# ProPrj_Business_Card_Macro_Pad_2025-06-1.net
KiCad netlist of a schematic drawn in EasyEDA Pro
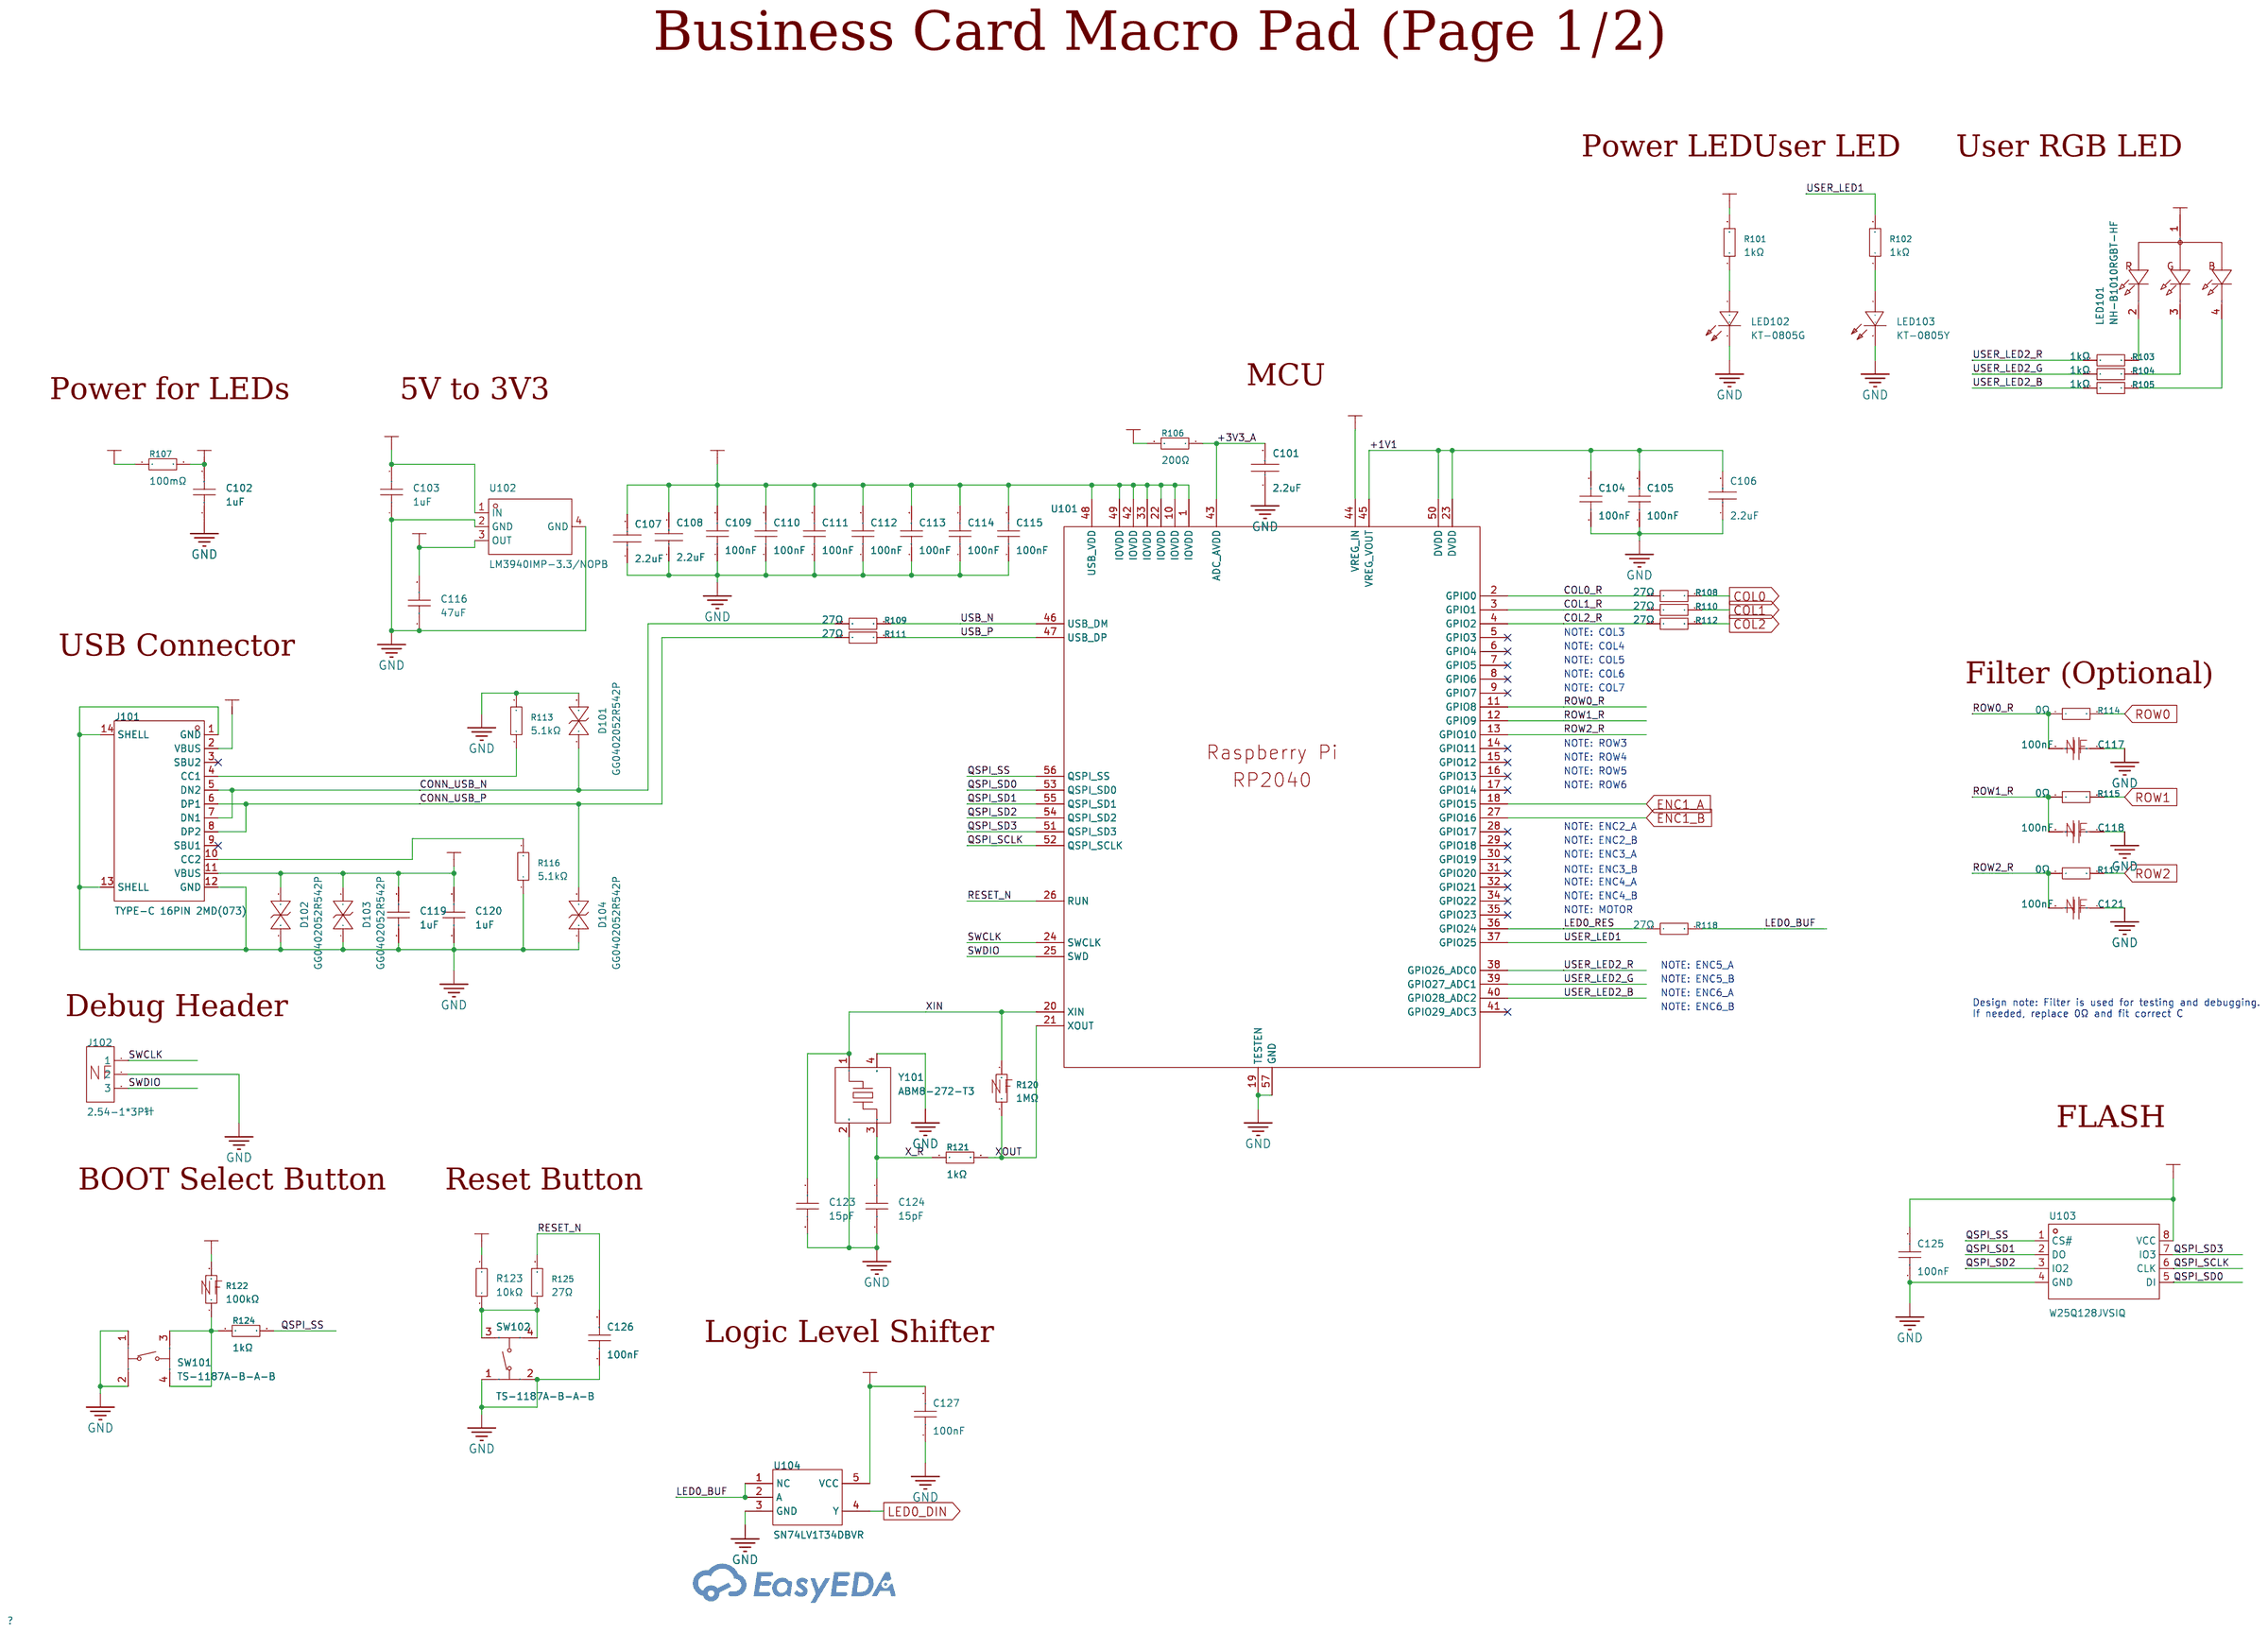
[diagram p0: MCU]
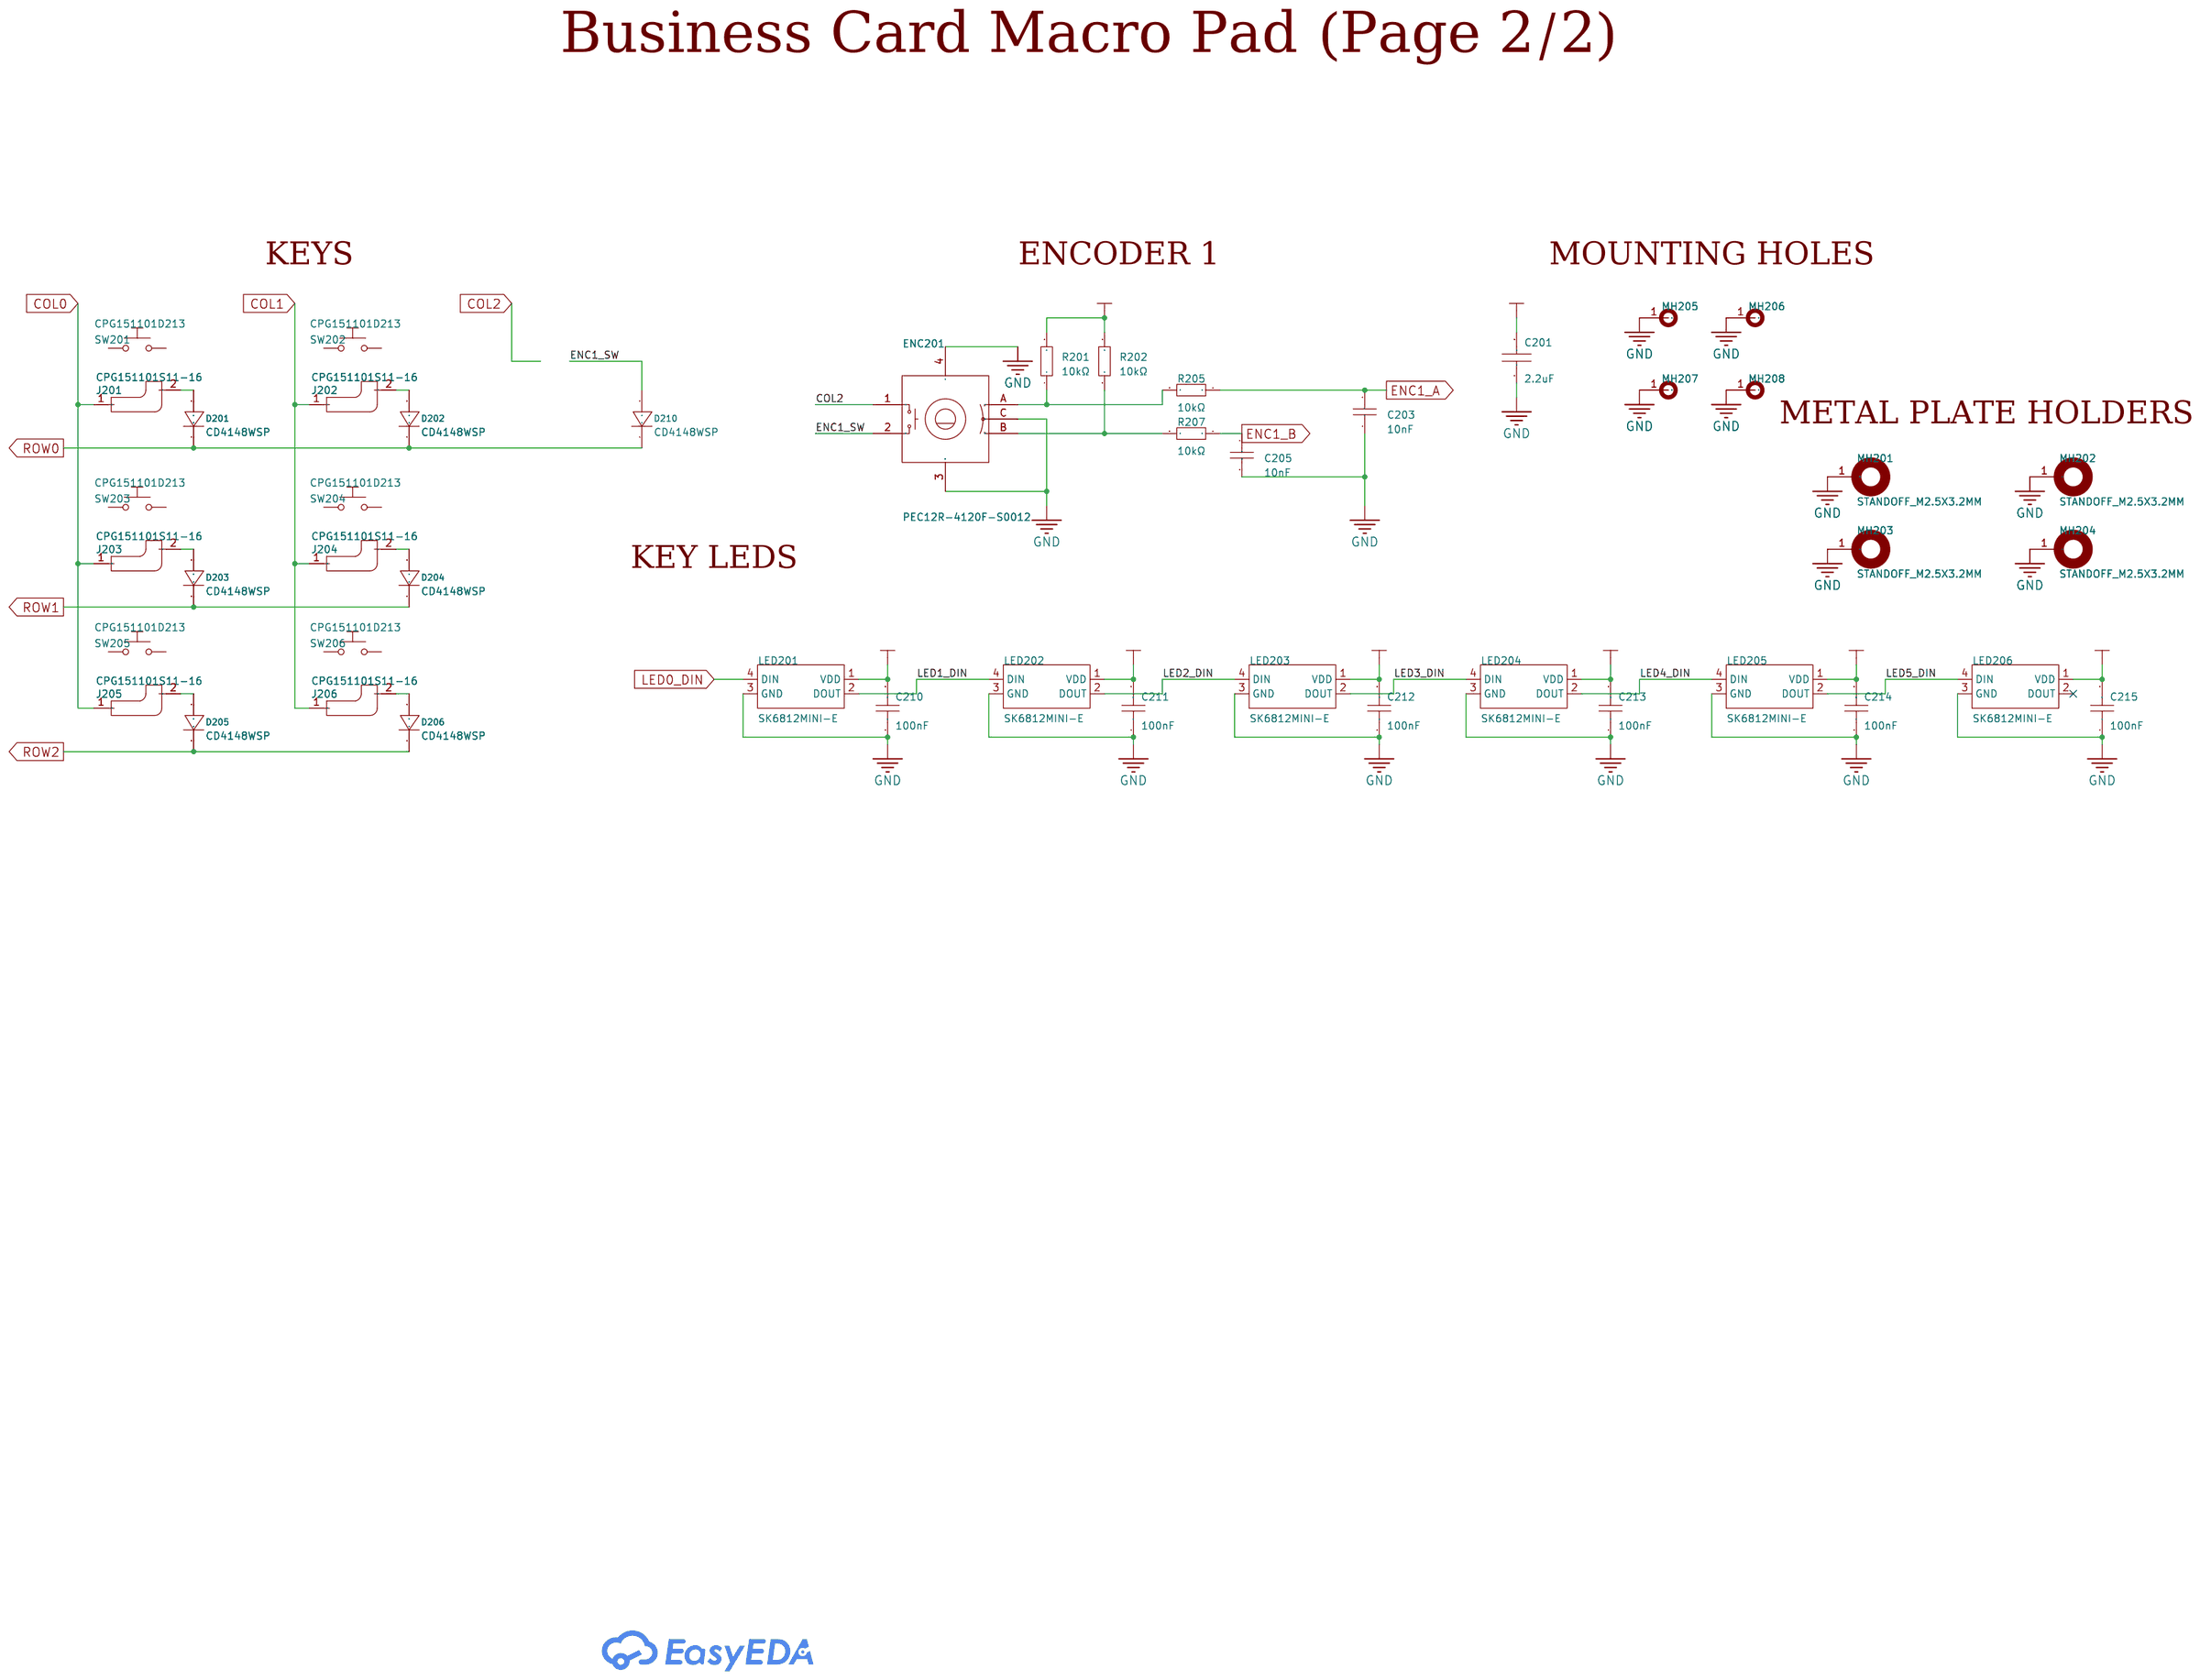
[diagram p1: OTHER]

(export (version "E")
  (design (tool "Eeschema 10.0.6"))
  (components
    (comp (ref "C101")
      (value "2.2uF")
      (footprint "easyedapro:C0402")
      (fields
        (field (name "Manufacturer Part") "CL05A225MQ5NSNC")
        (field (name "Manufacturer") "SAMSUNG(三星)")
      )
      (libsource (lib "easyedapro") (part "CL05A225MQ5NSNC"))
    )
    (comp (ref "C102")
      (value "1uF")
      (footprint "easyedapro:C0402")
      (fields
        (field (name "Manufacturer Part") "CL05A105KA5NQNC")
        (field (name "Manufacturer") "SAMSUNG(三星)")
      )
      (libsource (lib "easyedapro") (part "CL05A105KA5NQNC"))
    )
    (comp (ref "C103")
      (value "1uF")
      (footprint "easyedapro:C0402")
      (fields
        (field (name "Manufacturer Part") "CL05A105KA5NQNC")
        (field (name "Manufacturer") "SAMSUNG(三星)")
      )
      (libsource (lib "easyedapro") (part "CL05A105KA5NQNC"))
    )
    (comp (ref "C104")
      (value "100nF")
      (footprint "easyedapro:C0402")
      (fields
        (field (name "Manufacturer Part") "CL05B104KO5NNNC")
        (field (name "Manufacturer") "SAMSUNG(三星)")
      )
      (libsource (lib "easyedapro") (part "CL05B104KO5NNNC"))
    )
    (comp (ref "C105")
      (value "100nF")
      (footprint "easyedapro:C0402")
      (fields
        (field (name "Manufacturer Part") "CL05B104KO5NNNC")
        (field (name "Manufacturer") "SAMSUNG(三星)")
      )
      (libsource (lib "easyedapro") (part "CL05B104KO5NNNC"))
    )
    (comp (ref "C106")
      (value "2.2uF")
      (footprint "easyedapro:C0402")
      (fields
        (field (name "Manufacturer Part") "CL05A225MQ5NSNC")
        (field (name "Manufacturer") "SAMSUNG(三星)")
      )
      (libsource (lib "easyedapro") (part "CL05A225MQ5NSNC"))
    )
    (comp (ref "C107")
      (value "2.2uF")
      (footprint "easyedapro:C0402")
      (fields
        (field (name "Manufacturer Part") "CL05A225MQ5NSNC")
        (field (name "Manufacturer") "SAMSUNG(三星)")
      )
      (libsource (lib "easyedapro") (part "CL05A225MQ5NSNC"))
    )
    (comp (ref "C108")
      (value "2.2uF")
      (footprint "easyedapro:C0402")
      (fields
        (field (name "Manufacturer Part") "CL05A225MQ5NSNC")
        (field (name "Manufacturer") "SAMSUNG(三星)")
      )
      (libsource (lib "easyedapro") (part "CL05A225MQ5NSNC"))
    )
    (comp (ref "C109")
      (value "100nF")
      (footprint "easyedapro:C0402")
      (fields
        (field (name "Manufacturer Part") "CL05B104KO5NNNC")
        (field (name "Manufacturer") "SAMSUNG(三星)")
      )
      (libsource (lib "easyedapro") (part "CL05B104KO5NNNC"))
    )
    (comp (ref "C110")
      (value "100nF")
      (footprint "easyedapro:C0402")
      (fields
        (field (name "Manufacturer Part") "CL05B104KO5NNNC")
        (field (name "Manufacturer") "SAMSUNG(三星)")
      )
      (libsource (lib "easyedapro") (part "CL05B104KO5NNNC"))
    )
    (comp (ref "C111")
      (value "100nF")
      (footprint "easyedapro:C0402")
      (fields
        (field (name "Manufacturer Part") "CL05B104KO5NNNC")
        (field (name "Manufacturer") "SAMSUNG(三星)")
      )
      (libsource (lib "easyedapro") (part "CL05B104KO5NNNC"))
    )
    (comp (ref "C112")
      (value "100nF")
      (footprint "easyedapro:C0402")
      (fields
        (field (name "Manufacturer Part") "CL05B104KO5NNNC")
        (field (name "Manufacturer") "SAMSUNG(三星)")
      )
      (libsource (lib "easyedapro") (part "CL05B104KO5NNNC"))
    )
    (comp (ref "C113")
      (value "100nF")
      (footprint "easyedapro:C0402")
      (fields
        (field (name "Manufacturer Part") "CL05B104KO5NNNC")
        (field (name "Manufacturer") "SAMSUNG(三星)")
      )
      (libsource (lib "easyedapro") (part "CL05B104KO5NNNC"))
    )
    (comp (ref "C114")
      (value "100nF")
      (footprint "easyedapro:C0402")
      (fields
        (field (name "Manufacturer Part") "CL05B104KO5NNNC")
        (field (name "Manufacturer") "SAMSUNG(三星)")
      )
      (libsource (lib "easyedapro") (part "CL05B104KO5NNNC"))
    )
    (comp (ref "C115")
      (value "100nF")
      (footprint "easyedapro:C0402")
      (fields
        (field (name "Manufacturer Part") "CL05B104KO5NNNC")
        (field (name "Manufacturer") "SAMSUNG(三星)")
      )
      (libsource (lib "easyedapro") (part "CL05B104KO5NNNC"))
    )
    (comp (ref "C116")
      (value "47uF")
      (footprint "easyedapro:C1206")
      (fields
        (field (name "Manufacturer Part") "CL31A476MPHNNNE")
        (field (name "Manufacturer") "SAMSUNG(三星)")
      )
      (libsource (lib "easyedapro") (part "CL31A476MPHNNNE"))
    )
    (comp (ref "C117")
      (value "100nF")
      (footprint "easyedapro:C0402")
      (fields
        (field (name "Manufacturer Part") "CL05B104KO5NNNC")
        (field (name "Manufacturer") "SAMSUNG(三星)")
      )
      (libsource (lib "easyedapro") (part "CL05B104KO5NNNC"))
    )
    (comp (ref "C118")
      (value "100nF")
      (footprint "easyedapro:C0402")
      (fields
        (field (name "Manufacturer Part") "CL05B104KO5NNNC")
        (field (name "Manufacturer") "SAMSUNG(三星)")
      )
      (libsource (lib "easyedapro") (part "CL05B104KO5NNNC"))
    )
    (comp (ref "C119")
      (value "1uF")
      (footprint "easyedapro:C0402")
      (fields
        (field (name "Manufacturer Part") "CL05A105KA5NQNC")
        (field (name "Manufacturer") "SAMSUNG(三星)")
      )
      (libsource (lib "easyedapro") (part "CL05A105KA5NQNC"))
    )
    (comp (ref "C120")
      (value "1uF")
      (footprint "easyedapro:C0402")
      (fields
        (field (name "Manufacturer Part") "CL05A105KA5NQNC")
        (field (name "Manufacturer") "SAMSUNG(三星)")
      )
      (libsource (lib "easyedapro") (part "CL05A105KA5NQNC"))
    )
    (comp (ref "C121")
      (value "100nF")
      (footprint "easyedapro:C0402")
      (fields
        (field (name "Manufacturer Part") "CL05B104KO5NNNC")
        (field (name "Manufacturer") "SAMSUNG(三星)")
      )
      (libsource (lib "easyedapro") (part "CL05B104KO5NNNC"))
    )
    (comp (ref "C123")
      (value "15pF")
      (footprint "easyedapro:C0402")
      (fields
        (field (name "Manufacturer Part") "CL05C150JB5NNNC")
        (field (name "Manufacturer") "SAMSUNG(三星)")
      )
      (libsource (lib "easyedapro") (part "CL05C150JB5NNNC"))
    )
    (comp (ref "C124")
      (value "15pF")
      (footprint "easyedapro:C0402")
      (fields
        (field (name "Manufacturer Part") "CL05C150JB5NNNC")
        (field (name "Manufacturer") "SAMSUNG(三星)")
      )
      (libsource (lib "easyedapro") (part "CL05C150JB5NNNC"))
    )
    (comp (ref "C125")
      (value "100nF")
      (footprint "easyedapro:C0402")
      (fields
        (field (name "Manufacturer Part") "CL05B104KO5NNNC")
        (field (name "Manufacturer") "SAMSUNG(三星)")
      )
      (libsource (lib "easyedapro") (part "CL05B104KO5NNNC"))
    )
    (comp (ref "C126")
      (value "100nF")
      (footprint "easyedapro:C0402")
      (fields
        (field (name "Manufacturer Part") "CL05B104KO5NNNC")
        (field (name "Manufacturer") "SAMSUNG(三星)")
      )
      (libsource (lib "easyedapro") (part "CL05B104KO5NNNC"))
    )
    (comp (ref "C127")
      (value "100nF")
      (footprint "easyedapro:C0402")
      (fields
        (field (name "Manufacturer Part") "CL05B104KO5NNNC")
        (field (name "Manufacturer") "SAMSUNG(三星)")
      )
      (libsource (lib "easyedapro") (part "CL05B104KO5NNNC"))
    )
    (comp (ref "D101")
      (value "GG0402052R542P")
      (footprint "easyedapro:D0402-BI")
      (fields (field (name "Manufacturer") "Kyocera AVX"))
      (libsource (lib "easyedapro") (part "GG0402052R542P"))
    )
    (comp (ref "D102")
      (value "GG0402052R542P")
      (footprint "easyedapro:D0402-BI")
      (fields (field (name "Manufacturer") "Kyocera AVX"))
      (libsource (lib "easyedapro") (part "GG0402052R542P"))
    )
    (comp (ref "D103")
      (value "GG0402052R542P")
      (footprint "easyedapro:D0402-BI")
      (fields (field (name "Manufacturer") "Kyocera AVX"))
      (libsource (lib "easyedapro") (part "GG0402052R542P"))
    )
    (comp (ref "D104")
      (value "GG0402052R542P")
      (footprint "easyedapro:D0402-BI")
      (fields (field (name "Manufacturer") "Kyocera AVX"))
      (libsource (lib "easyedapro") (part "GG0402052R542P"))
    )
    (comp (ref "J101")
      (value "TYPE-C 16PIN 2MD(073)")
      (footprint "easyedapro:USB-C-SMD_TYPE-C-6PIN-2MD-073")
      (fields (field (name "Manufacturer") "SHOU HAN(首韩)"))
      (libsource (lib "easyedapro") (part "TYPE-C 16PIN 2MD(073)"))
    )
    (comp (ref "J102")
      (value "2.54-1*3P针")
      (footprint "easyedapro:HDR-TH_3P-P2.54-V-M-1")
      (fields (field (name "Manufacturer") "BOOMELE(博穆精密)"))
      (libsource (lib "easyedapro") (part "Header-Male-2.54_1x3"))
    )
    (comp (ref "LED101")
      (value "NH-B1010RGBT-HF")
      (footprint "easyedapro:LED-ARRAY-SMD_4P-L1.0-W1.0-TR_NH-B1010RGBT")
      (fields (field (name "Manufacturer") "国星光电"))
      (libsource (lib "easyedapro") (part "NH-B1010RGBT-HF_JO_v1.0"))
    )
    (comp (ref "LED102")
      (value "KT-0805G")
      (footprint "easyedapro:LED0805-R-RD")
      (fields (field (name "Manufacturer") "KENTO"))
      (libsource (lib "easyedapro") (part "0805G (Green)"))
    )
    (comp (ref "LED103")
      (value "KT-0805Y")
      (footprint "easyedapro:LED0805-R-RD")
      (fields (field (name "Manufacturer") "KENTO"))
      (libsource (lib "easyedapro") (part "17-21SUYC/TR8"))
    )
    (comp (ref "R101")
      (value "1kΩ")
      (footprint "easyedapro:R0402")
      (fields
        (field (name "Manufacturer Part") "0402WGF1001TCE")
        (field (name "Manufacturer") "UNI-ROYAL(厚声)")
      )
      (libsource (lib "easyedapro") (part "0402WGF1001TCE"))
    )
    (comp (ref "R102")
      (value "1kΩ")
      (footprint "easyedapro:R0402")
      (fields
        (field (name "Manufacturer Part") "0402WGF1001TCE")
        (field (name "Manufacturer") "UNI-ROYAL(厚声)")
      )
      (libsource (lib "easyedapro") (part "0402WGF1001TCE"))
    )
    (comp (ref "R103")
      (value "1kΩ")
      (footprint "easyedapro:R0402")
      (fields
        (field (name "Manufacturer Part") "0402WGF1001TCE")
        (field (name "Manufacturer") "UNI-ROYAL(厚声)")
      )
      (libsource (lib "easyedapro") (part "0402WGF1001TCE"))
    )
    (comp (ref "R104")
      (value "1kΩ")
      (footprint "easyedapro:R0402")
      (fields
        (field (name "Manufacturer Part") "0402WGF1001TCE")
        (field (name "Manufacturer") "UNI-ROYAL(厚声)")
      )
      (libsource (lib "easyedapro") (part "0402WGF1001TCE"))
    )
    (comp (ref "R105")
      (value "1kΩ")
      (footprint "easyedapro:R0402")
      (fields
        (field (name "Manufacturer Part") "0402WGF1001TCE")
        (field (name "Manufacturer") "UNI-ROYAL(厚声)")
      )
      (libsource (lib "easyedapro") (part "0402WGF1001TCE"))
    )
    (comp (ref "R106")
      (value "200Ω")
      (footprint "easyedapro:R0402")
      (fields
        (field (name "Manufacturer Part") "0402WGF2000TCE")
        (field (name "Manufacturer") "UNI-ROYAL(厚声)")
      )
      (libsource (lib "easyedapro") (part "0402WGF2000TCE"))
    )
    (comp (ref "R107")
      (value "100mΩ")
      (footprint "easyedapro:R1206")
      (fields
        (field (name "Manufacturer Part") "1206W4F100LT5E")
        (field (name "Manufacturer") "UNI-ROYAL(厚声)")
      )
      (libsource (lib "easyedapro") (part "1206W4F100LT5E"))
    )
    (comp (ref "R108")
      (value "27Ω")
      (footprint "easyedapro:R0402")
      (fields
        (field (name "Manufacturer Part") "0402WGF270JTCE")
        (field (name "Manufacturer") "UNI-ROYAL(厚声)")
      )
      (libsource (lib "easyedapro") (part "0402WGF270JTCE"))
    )
    (comp (ref "R109")
      (value "27Ω")
      (footprint "easyedapro:R0402")
      (fields
        (field (name "Manufacturer Part") "0402WGF270JTCE")
        (field (name "Manufacturer") "UNI-ROYAL(厚声)")
      )
      (libsource (lib "easyedapro") (part "0402WGF270JTCE"))
    )
    (comp (ref "R110")
      (value "27Ω")
      (footprint "easyedapro:R0402")
      (fields
        (field (name "Manufacturer Part") "0402WGF270JTCE")
        (field (name "Manufacturer") "UNI-ROYAL(厚声)")
      )
      (libsource (lib "easyedapro") (part "0402WGF270JTCE"))
    )
    (comp (ref "R111")
      (value "27Ω")
      (footprint "easyedapro:R0402")
      (fields
        (field (name "Manufacturer Part") "0402WGF270JTCE")
        (field (name "Manufacturer") "UNI-ROYAL(厚声)")
      )
      (libsource (lib "easyedapro") (part "0402WGF270JTCE"))
    )
    (comp (ref "R112")
      (value "27Ω")
      (footprint "easyedapro:R0402")
      (fields
        (field (name "Manufacturer Part") "0402WGF270JTCE")
        (field (name "Manufacturer") "UNI-ROYAL(厚声)")
      )
      (libsource (lib "easyedapro") (part "0402WGF270JTCE"))
    )
    (comp (ref "R113")
      (value "5.1kΩ")
      (footprint "easyedapro:R0402")
      (fields
        (field (name "Manufacturer Part") "0402WGF5101TCE")
        (field (name "Manufacturer") "UNI-ROYAL(厚声)")
      )
      (libsource (lib "easyedapro") (part "0402WGF5101TCE"))
    )
    (comp (ref "R114")
      (value "0Ω")
      (footprint "easyedapro:R0402")
      (fields
        (field (name "Manufacturer Part") "0402WGF0000TCE")
        (field (name "Manufacturer") "UNI-ROYAL(厚声)")
      )
      (libsource (lib "easyedapro") (part "0402WGF0000TCE"))
    )
    (comp (ref "R115")
      (value "0Ω")
      (footprint "easyedapro:R0402")
      (fields
        (field (name "Manufacturer Part") "0402WGF0000TCE")
        (field (name "Manufacturer") "UNI-ROYAL(厚声)")
      )
      (libsource (lib "easyedapro") (part "0402WGF0000TCE"))
    )
    (comp (ref "R116")
      (value "5.1kΩ")
      (footprint "easyedapro:R0402")
      (fields
        (field (name "Manufacturer Part") "0402WGF5101TCE")
        (field (name "Manufacturer") "UNI-ROYAL(厚声)")
      )
      (libsource (lib "easyedapro") (part "0402WGF5101TCE"))
    )
    (comp (ref "R117")
      (value "0Ω")
      (footprint "easyedapro:R0402")
      (fields
        (field (name "Manufacturer Part") "0402WGF0000TCE")
        (field (name "Manufacturer") "UNI-ROYAL(厚声)")
      )
      (libsource (lib "easyedapro") (part "0402WGF0000TCE"))
    )
    (comp (ref "R118")
      (value "27Ω")
      (footprint "easyedapro:R0402")
      (fields
        (field (name "Manufacturer Part") "0402WGF270JTCE")
        (field (name "Manufacturer") "UNI-ROYAL(厚声)")
      )
      (libsource (lib "easyedapro") (part "0402WGF270JTCE"))
    )
    (comp (ref "R120")
      (value "1MΩ")
      (footprint "easyedapro:R0402")
      (fields
        (field (name "Manufacturer Part") "0402WGF1004TCE")
        (field (name "Manufacturer") "UNI-ROYAL(厚声)")
      )
      (libsource (lib "easyedapro") (part "0402WGF1004TCE"))
    )
    (comp (ref "R121")
      (value "1kΩ")
      (footprint "easyedapro:R0402")
      (fields
        (field (name "Manufacturer Part") "0402WGF1001TCE")
        (field (name "Manufacturer") "UNI-ROYAL(厚声)")
      )
      (libsource (lib "easyedapro") (part "0402WGF1001TCE"))
    )
    (comp (ref "R122")
      (value "100kΩ")
      (footprint "easyedapro:R0402")
      (fields
        (field (name "Manufacturer Part") "0402WGF1003TCE")
        (field (name "Manufacturer") "UNI-ROYAL(厚声)")
      )
      (libsource (lib "easyedapro") (part "0402WGF1003TCE"))
    )
    (comp (ref "R123")
      (value "10kΩ")
      (footprint "easyedapro:R0402")
      (fields
        (field (name "Manufacturer Part") "0402WGF1002TCE")
        (field (name "Manufacturer") "UNI-ROYAL(厚声)")
      )
      (libsource (lib "easyedapro") (part "0402WGF1002TCE"))
    )
    (comp (ref "R124")
      (value "1kΩ")
      (footprint "easyedapro:R0402")
      (fields
        (field (name "Manufacturer Part") "0402WGF1001TCE")
        (field (name "Manufacturer") "UNI-ROYAL(厚声)")
      )
      (libsource (lib "easyedapro") (part "0402WGF1001TCE"))
    )
    (comp (ref "R125")
      (value "27Ω")
      (footprint "easyedapro:R0402")
      (fields
        (field (name "Manufacturer Part") "0402WGF270JTCE")
        (field (name "Manufacturer") "UNI-ROYAL(厚声)")
      )
      (libsource (lib "easyedapro") (part "0402WGF270JTCE"))
    )
    (comp (ref "SW101")
      (value "TS-1187A-B-A-B")
      (footprint "easyedapro:SW-SMD_4P-L5.1-W5.1-P3.70-LS6.5-TL_H1.5")
      (fields (field (name "Manufacturer") "XKB Connectivity(中国星坤)"))
      (libsource (lib "easyedapro") (part "TS-1187A-B-A-B"))
    )
    (comp (ref "SW102")
      (value "TS-1187A-B-A-B")
      (footprint "easyedapro:SW-SMD_4P-L5.1-W5.1-P3.70-LS6.5-TL_H1.5")
      (fields (field (name "Manufacturer") "XKB Connectivity(中国星坤)"))
      (libsource (lib "easyedapro") (part "TS-1187A-B-A-B"))
    )
    (comp (ref "U101")
      (value "RP2040")
      (footprint "easyedapro:LQFN-56_L7.0-W7.0-P0.4-EP")
      (fields (field (name "Manufacturer") "Raspberry Pi(树莓派)"))
      (libsource (lib "easyedapro") (part "RP2040_C2040_jo_v1.0"))
    )
    (comp (ref "U102")
      (value "LM3940IMP-3.3/NOPB")
      (footprint "easyedapro:SOT-223_L6.5-W3.5-P2.30-LS7.0-BR")
      (fields (field (name "Manufacturer") "TI(德州仪器)"))
      (libsource (lib "easyedapro") (part "LM3940IMP-3.3/NOPB"))
    )
    (comp (ref "U103")
      (value "W25Q128JVSIQ")
      (footprint "easyedapro:SOIC-8_L5.3-W5.3-P1.27-LS8.0-BL")
      (fields (field (name "Manufacturer") "WINBOND(华邦)"))
      (libsource (lib "easyedapro") (part "W25Q128JVSIQTR"))
    )
    (comp (ref "U104")
      (value "SN74LV1T34DBVR")
      (footprint "easyedapro:SOT-23-5_L2.9-W1.6-P0.95-LS2.8-BR")
      (fields (field (name "Manufacturer") "TI(德州仪器)"))
      (libsource (lib "easyedapro") (part "SN74LV1T34DBVR_JO_v1.0"))
    )
    (comp (ref "Y101")
      (value "ABM8-272-T3")
      (footprint "easyedapro:CRYSTAL-SMD_4P-L3.2-W2.5-BL")
      (fields (field (name "Manufacturer") "ABRACON"))
      (libsource (lib "easyedapro") (part "ABM8-272-T3_C20625731"))
    )
    (comp (ref "C201")
      (value "2.2uF")
      (footprint "easyedapro:C0402")
      (fields
        (field (name "Manufacturer Part") "CL05A225MQ5NSNC")
        (field (name "Manufacturer") "SAMSUNG(三星)")
      )
      (libsource (lib "easyedapro") (part "CL05A225MQ5NSNC"))
    )
    (comp (ref "C203")
      (value "10nF")
      (footprint "easyedapro:C0402")
      (fields
        (field (name "Manufacturer Part") "CL05B103KB5NNNC")
        (field (name "Manufacturer") "SAMSUNG(三星)")
      )
      (libsource (lib "easyedapro") (part "CL05B103KB5NNNC"))
    )
    (comp (ref "C205")
      (value "10nF")
      (footprint "easyedapro:C0402")
      (fields
        (field (name "Manufacturer Part") "CL05B103KB5NNNC")
        (field (name "Manufacturer") "SAMSUNG(三星)")
      )
      (libsource (lib "easyedapro") (part "CL05B103KB5NNNC"))
    )
    (comp (ref "C210")
      (value "100nF")
      (footprint "easyedapro:C0402")
      (fields
        (field (name "Manufacturer Part") "CL05B104KO5NNNC")
        (field (name "Manufacturer") "SAMSUNG(三星)")
      )
      (libsource (lib "easyedapro") (part "CL05B104KO5NNNC"))
    )
    (comp (ref "C211")
      (value "100nF")
      (footprint "easyedapro:C0402")
      (fields
        (field (name "Manufacturer Part") "CL05B104KO5NNNC")
        (field (name "Manufacturer") "SAMSUNG(三星)")
      )
      (libsource (lib "easyedapro") (part "CL05B104KO5NNNC"))
    )
    (comp (ref "C212")
      (value "100nF")
      (footprint "easyedapro:C0402")
      (fields
        (field (name "Manufacturer Part") "CL05B104KO5NNNC")
        (field (name "Manufacturer") "SAMSUNG(三星)")
      )
      (libsource (lib "easyedapro") (part "CL05B104KO5NNNC"))
    )
    (comp (ref "C213")
      (value "100nF")
      (footprint "easyedapro:C0402")
      (fields
        (field (name "Manufacturer Part") "CL05B104KO5NNNC")
        (field (name "Manufacturer") "SAMSUNG(三星)")
      )
      (libsource (lib "easyedapro") (part "CL05B104KO5NNNC"))
    )
    (comp (ref "C214")
      (value "100nF")
      (footprint "easyedapro:C0402")
      (fields
        (field (name "Manufacturer Part") "CL05B104KO5NNNC")
        (field (name "Manufacturer") "SAMSUNG(三星)")
      )
      (libsource (lib "easyedapro") (part "CL05B104KO5NNNC"))
    )
    (comp (ref "C215")
      (value "100nF")
      (footprint "easyedapro:C0402")
      (fields
        (field (name "Manufacturer Part") "CL05B104KO5NNNC")
        (field (name "Manufacturer") "SAMSUNG(三星)")
      )
      (libsource (lib "easyedapro") (part "CL05B104KO5NNNC"))
    )
    (comp (ref "D201")
      (value "CD4148WSP")
      (footprint "easyedapro:D0805-RD")
      (fields (field (name "Manufacturer") "LIZ(丽智电子)"))
      (libsource (lib "easyedapro") (part "CD4148WSP-C109001"))
    )
    (comp (ref "D202")
      (value "CD4148WSP")
      (footprint "easyedapro:D0805-RD")
      (fields (field (name "Manufacturer") "LIZ(丽智电子)"))
      (libsource (lib "easyedapro") (part "CD4148WSP-C109001"))
    )
    (comp (ref "D203")
      (value "CD4148WSP")
      (footprint "easyedapro:D0805-RD")
      (fields (field (name "Manufacturer") "LIZ(丽智电子)"))
      (libsource (lib "easyedapro") (part "CD4148WSP-C109001"))
    )
    (comp (ref "D204")
      (value "CD4148WSP")
      (footprint "easyedapro:D0805-RD")
      (fields (field (name "Manufacturer") "LIZ(丽智电子)"))
      (libsource (lib "easyedapro") (part "CD4148WSP-C109001"))
    )
    (comp (ref "D205")
      (value "CD4148WSP")
      (footprint "easyedapro:D0805-RD")
      (fields (field (name "Manufacturer") "LIZ(丽智电子)"))
      (libsource (lib "easyedapro") (part "CD4148WSP-C109001"))
    )
    (comp (ref "D206")
      (value "CD4148WSP")
      (footprint "easyedapro:D0805-RD")
      (fields (field (name "Manufacturer") "LIZ(丽智电子)"))
      (libsource (lib "easyedapro") (part "CD4148WSP-C109001"))
    )
    (comp (ref "D210")
      (value "CD4148WSP")
      (footprint "easyedapro:D0805-RD")
      (fields (field (name "Manufacturer") "LIZ(丽智电子)"))
      (libsource (lib "easyedapro") (part "CD4148WSP-C109001"))
    )
    (comp (ref "ENC201")
      (value "PEC12R-4120F-S0012")
      (footprint "easyedapro:SW-TH_PEC12R-4120F-S0012")
      (fields (field (name "Manufacturer") "BOURNS"))
      (libsource (lib "easyedapro") (part "PEC12R-4120F-S0012_JO_v1.0"))
    )
    (comp (ref "J201")
      (value "CPG151101S11-16")
      (footprint "easyedapro:SMD_KEYBOARD-SW")
      (fields (field (name "Manufacturer") "Kailh(凯华)"))
      (libsource (lib "easyedapro") (part "CPG151101S11-16_JO_v1.0"))
    )
    (comp (ref "J202")
      (value "CPG151101S11-16")
      (footprint "easyedapro:SMD_KEYBOARD-SW")
      (fields (field (name "Manufacturer") "Kailh(凯华)"))
      (libsource (lib "easyedapro") (part "CPG151101S11-16_JO_v1.0"))
    )
    (comp (ref "J203")
      (value "CPG151101S11-16")
      (footprint "easyedapro:SMD_KEYBOARD-SW")
      (fields (field (name "Manufacturer") "Kailh(凯华)"))
      (libsource (lib "easyedapro") (part "CPG151101S11-16_JO_v1.0"))
    )
    (comp (ref "J204")
      (value "CPG151101S11-16")
      (footprint "easyedapro:SMD_KEYBOARD-SW")
      (fields (field (name "Manufacturer") "Kailh(凯华)"))
      (libsource (lib "easyedapro") (part "CPG151101S11-16_JO_v1.0"))
    )
    (comp (ref "J205")
      (value "CPG151101S11-16")
      (footprint "easyedapro:SMD_KEYBOARD-SW")
      (fields (field (name "Manufacturer") "Kailh(凯华)"))
      (libsource (lib "easyedapro") (part "CPG151101S11-16_JO_v1.0"))
    )
    (comp (ref "J206")
      (value "CPG151101S11-16")
      (footprint "easyedapro:SMD_KEYBOARD-SW")
      (fields (field (name "Manufacturer") "Kailh(凯华)"))
      (libsource (lib "easyedapro") (part "CPG151101S11-16_JO_v1.0"))
    )
    (comp (ref "LED201")
      (value "SK6812MINI-E")
      (footprint "easyedapro:LED-SMD_L3.2-W2.8-LS5.9_SK6812MINI-E")
      (fields (field (name "Manufacturer") "欧思科光电"))
      (libsource (lib "easyedapro") (part "SK6812MINI-E_C5149201"))
    )
    (comp (ref "LED202")
      (value "SK6812MINI-E")
      (footprint "easyedapro:LED-SMD_L3.2-W2.8-LS5.9_SK6812MINI-E")
      (fields (field (name "Manufacturer") "欧思科光电"))
      (libsource (lib "easyedapro") (part "SK6812MINI-E_C5149201"))
    )
    (comp (ref "LED203")
      (value "SK6812MINI-E")
      (footprint "easyedapro:LED-SMD_L3.2-W2.8-LS5.9_SK6812MINI-E")
      (fields (field (name "Manufacturer") "欧思科光电"))
      (libsource (lib "easyedapro") (part "SK6812MINI-E_C5149201"))
    )
    (comp (ref "LED204")
      (value "SK6812MINI-E")
      (footprint "easyedapro:LED-SMD_L3.2-W2.8-LS5.9_SK6812MINI-E")
      (fields (field (name "Manufacturer") "欧思科光电"))
      (libsource (lib "easyedapro") (part "SK6812MINI-E_C5149201"))
    )
    (comp (ref "LED205")
      (value "SK6812MINI-E")
      (footprint "easyedapro:LED-SMD_L3.2-W2.8-LS5.9_SK6812MINI-E")
      (fields (field (name "Manufacturer") "欧思科光电"))
      (libsource (lib "easyedapro") (part "SK6812MINI-E_C5149201"))
    )
    (comp (ref "LED206")
      (value "SK6812MINI-E")
      (footprint "easyedapro:LED-SMD_L3.2-W2.8-LS5.9_SK6812MINI-E")
      (fields (field (name "Manufacturer") "欧思科光电"))
      (libsource (lib "easyedapro") (part "SK6812MINI-E_C5149201"))
    )
    (comp (ref "MH201")
      (value "STANDOFF_M2.5X3.2MM")
      (footprint "easyedapro:STANDOFF_M2.5X3.5MM_JO_v1.0")
      (description "Standoff, Steel, M2.5, Hex Female-Female, 3.5 mm, 4.9 mm")
      (fields (field (name "Manufacturer") "WURTH ELEKTRONIK"))
      (libsource (lib "easyedapro") (part "9774035151R_JO_v1.0"))
    )
    (comp (ref "MH202")
      (value "STANDOFF_M2.5X3.2MM")
      (footprint "easyedapro:STANDOFF_M2.5X3.5MM_JO_v1.0")
      (description "Standoff, Steel, M2.5, Hex Female-Female, 3.5 mm, 4.9 mm")
      (fields (field (name "Manufacturer") "WURTH ELEKTRONIK"))
      (libsource (lib "easyedapro") (part "9774035151R_JO_v1.0"))
    )
    (comp (ref "MH203")
      (value "STANDOFF_M2.5X3.2MM")
      (footprint "easyedapro:STANDOFF_M2.5X3.5MM_JO_v1.0")
      (description "Standoff, Steel, M2.5, Hex Female-Female, 3.5 mm, 4.9 mm")
      (fields (field (name "Manufacturer") "WURTH ELEKTRONIK"))
      (libsource (lib "easyedapro") (part "9774035151R_JO_v1.0"))
    )
    (comp (ref "MH204")
      (value "STANDOFF_M2.5X3.2MM")
      (footprint "easyedapro:STANDOFF_M2.5X3.5MM_JO_v1.0")
      (description "Standoff, Steel, M2.5, Hex Female-Female, 3.5 mm, 4.9 mm")
      (fields (field (name "Manufacturer") "WURTH ELEKTRONIK"))
      (libsource (lib "easyedapro") (part "9774035151R_JO_v1.0"))
    )
    (comp (ref "MH205")
      (value "~")
      (footprint "easyedapro:MH_7.5X3.2MM_JO_v1.0")
      (libsource (lib "easyedapro") (part "MH_JO_copy_of_RF1_V1.0"))
    )
    (comp (ref "MH206")
      (value "~")
      (footprint "easyedapro:MH_7.5X3.2MM_JO_v1.0")
      (libsource (lib "easyedapro") (part "MH_JO_copy_of_RF1_V1.0"))
    )
    (comp (ref "MH207")
      (value "~")
      (footprint "easyedapro:MH_7.5X3.2MM_JO_v1.0")
      (libsource (lib "easyedapro") (part "MH_JO_copy_of_RF1_V1.0"))
    )
    (comp (ref "MH208")
      (value "~")
      (footprint "easyedapro:MH_7.5X3.2MM_JO_v1.0")
      (libsource (lib "easyedapro") (part "MH_JO_copy_of_RF1_V1.0"))
    )
    (comp (ref "R201")
      (value "10kΩ")
      (footprint "easyedapro:R0402")
      (fields
        (field (name "Manufacturer Part") "0402WGF1002TCE")
        (field (name "Manufacturer") "UNI-ROYAL(厚声)")
      )
      (libsource (lib "easyedapro") (part "0402WGF1002TCE"))
    )
    (comp (ref "R202")
      (value "10kΩ")
      (footprint "easyedapro:R0402")
      (fields
        (field (name "Manufacturer Part") "0402WGF1002TCE")
        (field (name "Manufacturer") "UNI-ROYAL(厚声)")
      )
      (libsource (lib "easyedapro") (part "0402WGF1002TCE"))
    )
    (comp (ref "R205")
      (value "10kΩ")
      (footprint "easyedapro:R0402")
      (fields
        (field (name "Manufacturer Part") "0402WGF1002TCE")
        (field (name "Manufacturer") "UNI-ROYAL(厚声)")
      )
      (libsource (lib "easyedapro") (part "0402WGF1002TCE"))
    )
    (comp (ref "R207")
      (value "10kΩ")
      (footprint "easyedapro:R0402")
      (fields
        (field (name "Manufacturer Part") "0402WGF1002TCE")
        (field (name "Manufacturer") "UNI-ROYAL(厚声)")
      )
      (libsource (lib "easyedapro") (part "0402WGF1002TCE"))
    )
    (comp (ref "SW201")
      (value "CPG151101D213")
      (footprint "easyedapro:KEY-TH_CPG151101D21X")
      (fields (field (name "Manufacturer") "Kailh(凯华)"))
      (libsource (lib "easyedapro") (part "CPG151101D213_JO_v1.0"))
    )
    (comp (ref "SW202")
      (value "CPG151101D213")
      (footprint "easyedapro:KEY-TH_CPG151101D21X")
      (fields (field (name "Manufacturer") "Kailh(凯华)"))
      (libsource (lib "easyedapro") (part "CPG151101D213_JO_v1.0"))
    )
    (comp (ref "SW203")
      (value "CPG151101D213")
      (footprint "easyedapro:KEY-TH_CPG151101D21X")
      (fields (field (name "Manufacturer") "Kailh(凯华)"))
      (libsource (lib "easyedapro") (part "CPG151101D213_JO_v1.0"))
    )
    (comp (ref "SW204")
      (value "CPG151101D213")
      (footprint "easyedapro:KEY-TH_CPG151101D21X")
      (fields (field (name "Manufacturer") "Kailh(凯华)"))
      (libsource (lib "easyedapro") (part "CPG151101D213_JO_v1.0"))
    )
    (comp (ref "SW205")
      (value "CPG151101D213")
      (footprint "easyedapro:KEY-TH_CPG151101D21X")
      (fields (field (name "Manufacturer") "Kailh(凯华)"))
      (libsource (lib "easyedapro") (part "CPG151101D213_JO_v1.0"))
    )
    (comp (ref "SW206")
      (value "CPG151101D213")
      (footprint "easyedapro:KEY-TH_CPG151101D21X")
      (fields (field (name "Manufacturer") "Kailh(凯华)"))
      (libsource (lib "easyedapro") (part "CPG151101D213_JO_v1.0"))
    )
  )
  (nets
    (net (code "1") (name "+1V1") (class "Default")
      (node (ref "C104") (pin "2") (pinfunction "2_2") (pintype "unspecified"))
      (node (ref "C105") (pin "2") (pinfunction "2_2") (pintype "unspecified"))
      (node (ref "C106") (pin "2") (pinfunction "2_2") (pintype "unspecified"))
      (node (ref "U101") (pin "23") (pinfunction "DVDD_23") (pintype "bidirectional"))
      (node (ref "U101") (pin "45") (pinfunction "VREG_VOUT_45") (pintype "bidirectional"))
      (node (ref "U101") (pin "50") (pinfunction "DVDD_50") (pintype "bidirectional"))
    )
    (net (code "2") (name "+3V3") (class "Default")
      (node (ref "C107") (pin "2") (pinfunction "2_2") (pintype "unspecified"))
      (node (ref "C108") (pin "2") (pinfunction "2_2") (pintype "unspecified"))
      (node (ref "C109") (pin "2") (pinfunction "2_2") (pintype "unspecified"))
      (node (ref "C110") (pin "2") (pinfunction "2_2") (pintype "unspecified"))
      (node (ref "C111") (pin "2") (pinfunction "2_2") (pintype "unspecified"))
      (node (ref "C112") (pin "2") (pinfunction "2_2") (pintype "unspecified"))
      (node (ref "C113") (pin "2") (pinfunction "2_2") (pintype "unspecified"))
      (node (ref "C114") (pin "2") (pinfunction "2_2") (pintype "unspecified"))
      (node (ref "C115") (pin "2") (pinfunction "2_2") (pintype "unspecified"))
      (node (ref "C116") (pin "2") (pinfunction "2_2") (pintype "unspecified"))
      (node (ref "C125") (pin "2") (pinfunction "2_2") (pintype "unspecified"))
      (node (ref "C201") (pin "2") (pinfunction "2_2") (pintype "unspecified"))
      (node (ref "LED101") (pin "1") (pinfunction "+_1") (pintype "unspecified"))
      (node (ref "R101") (pin "2") (pinfunction "2_2") (pintype "input"))
      (node (ref "R106") (pin "2") (pinfunction "2_2") (pintype "input"))
      (node (ref "R122") (pin "2") (pinfunction "2_2") (pintype "input"))
      (node (ref "R123") (pin "2") (pinfunction "2_2") (pintype "input"))
      (node (ref "R201") (pin "2") (pinfunction "2_2") (pintype "input"))
      (node (ref "R202") (pin "2") (pinfunction "2_2") (pintype "input"))
      (node (ref "U101") (pin "1") (pinfunction "IOVDD_1") (pintype "bidirectional"))
      (node (ref "U101") (pin "10") (pinfunction "IOVDD_10") (pintype "bidirectional"))
      (node (ref "U101") (pin "22") (pinfunction "IOVDD_22") (pintype "bidirectional"))
      (node (ref "U101") (pin "33") (pinfunction "IOVDD_33") (pintype "bidirectional"))
      (node (ref "U101") (pin "42") (pinfunction "IOVDD_42") (pintype "bidirectional"))
      (node (ref "U101") (pin "44") (pinfunction "VREG_IN_44") (pintype "bidirectional"))
      (node (ref "U101") (pin "48") (pinfunction "USB_VDD_48") (pintype "bidirectional"))
      (node (ref "U101") (pin "49") (pinfunction "IOVDD_49") (pintype "bidirectional"))
      (node (ref "U102") (pin "3") (pinfunction "OUT_3") (pintype "unspecified"))
      (node (ref "U103") (pin "8") (pinfunction "VCC_8") (pintype "unspecified"))
    )
    (net (code "3") (name "+3V3_A") (class "Default")
      (node (ref "C101") (pin "2") (pinfunction "2_2") (pintype "unspecified"))
      (node (ref "R106") (pin "1") (pinfunction "1_1") (pintype "input"))
      (node (ref "U101") (pin "43") (pinfunction "ADC_AVDD_43") (pintype "bidirectional"))
    )
    (net (code "4") (name "+5V_LEDS") (class "Default")
      (node (ref "C102") (pin "2") (pinfunction "2_2") (pintype "unspecified"))
      (node (ref "C210") (pin "2") (pinfunction "2_2") (pintype "unspecified"))
      (node (ref "C211") (pin "2") (pinfunction "2_2") (pintype "unspecified"))
      (node (ref "C212") (pin "2") (pinfunction "2_2") (pintype "unspecified"))
      (node (ref "C213") (pin "2") (pinfunction "2_2") (pintype "unspecified"))
      (node (ref "C214") (pin "2") (pinfunction "2_2") (pintype "unspecified"))
      (node (ref "C215") (pin "2") (pinfunction "2_2") (pintype "unspecified"))
      (node (ref "LED201") (pin "1") (pinfunction "VDD_1") (pintype "unspecified"))
      (node (ref "LED202") (pin "1") (pinfunction "VDD_1") (pintype "unspecified"))
      (node (ref "LED203") (pin "1") (pinfunction "VDD_1") (pintype "unspecified"))
      (node (ref "LED204") (pin "1") (pinfunction "VDD_1") (pintype "unspecified"))
      (node (ref "LED205") (pin "1") (pinfunction "VDD_1") (pintype "unspecified"))
      (node (ref "LED206") (pin "1") (pinfunction "VDD_1") (pintype "unspecified"))
      (node (ref "R107") (pin "2") (pinfunction "2_2") (pintype "input"))
    )
    (net (code "5") (name "+5V_USB") (class "Default")
      (node (ref "C103") (pin "2") (pinfunction "2_2") (pintype "unspecified"))
      (node (ref "C119") (pin "2") (pinfunction "2_2") (pintype "unspecified"))
      (node (ref "C120") (pin "2") (pinfunction "2_2") (pintype "unspecified"))
      (node (ref "C127") (pin "2") (pinfunction "2_2") (pintype "unspecified"))
      (node (ref "D102") (pin "2") (pinfunction "2_2") (pintype "unspecified"))
      (node (ref "D103") (pin "2") (pinfunction "2_2") (pintype "unspecified"))
      (node (ref "J101") (pin "11") (pinfunction "VBUS_11") (pintype "unspecified"))
      (node (ref "J101") (pin "2") (pinfunction "VBUS_2") (pintype "unspecified"))
      (node (ref "R107") (pin "1") (pinfunction "1_1") (pintype "input"))
      (node (ref "U102") (pin "1") (pinfunction "IN_1") (pintype "unspecified"))
      (node (ref "U104") (pin "5") (pinfunction "VCC_5") (pintype "unspecified"))
    )
    (net (code "6") (name "COL0") (class "Default")
      (node (ref "J201") (pin "1") (pinfunction "1_1") (pintype "input"))
      (node (ref "J203") (pin "1") (pinfunction "1_1") (pintype "input"))
      (node (ref "J205") (pin "1") (pinfunction "1_1") (pintype "input"))
      (node (ref "R108") (pin "2") (pinfunction "2_2") (pintype "input"))
    )
    (net (code "7") (name "COL0_R") (class "Default")
      (node (ref "R108") (pin "1") (pinfunction "1_1") (pintype "input"))
      (node (ref "U101") (pin "2") (pinfunction "GPIO0_2") (pintype "bidirectional"))
    )
    (net (code "8") (name "COL1") (class "Default")
      (node (ref "J202") (pin "1") (pinfunction "1_1") (pintype "input"))
      (node (ref "J204") (pin "1") (pinfunction "1_1") (pintype "input"))
      (node (ref "J206") (pin "1") (pinfunction "1_1") (pintype "input"))
      (node (ref "R110") (pin "2") (pinfunction "2_2") (pintype "input"))
    )
    (net (code "9") (name "COL1_R") (class "Default")
      (node (ref "R110") (pin "1") (pinfunction "1_1") (pintype "input"))
      (node (ref "U101") (pin "3") (pinfunction "GPIO1_3") (pintype "bidirectional"))
    )
    (net (code "10") (name "COL2") (class "Default")
      (node (ref "ENC201") (pin "1") (pinfunction "1_1") (pintype "input"))
      (node (ref "R112") (pin "2") (pinfunction "2_2") (pintype "input"))
    )
    (net (code "11") (name "COL2_R") (class "Default")
      (node (ref "R112") (pin "1") (pinfunction "1_1") (pintype "input"))
      (node (ref "U101") (pin "4") (pinfunction "GPIO2_4") (pintype "bidirectional"))
    )
    (net (code "12") (name "CONN_USB_N") (class "Default")
      (node (ref "D101") (pin "1") (pinfunction "1_1") (pintype "unspecified"))
      (node (ref "J101") (pin "5") (pinfunction "DN2_5") (pintype "unspecified"))
      (node (ref "J101") (pin "7") (pinfunction "DN1_7") (pintype "unspecified"))
      (node (ref "R109") (pin "1") (pinfunction "1_1") (pintype "input"))
    )
    (net (code "13") (name "CONN_USB_P") (class "Default")
      (node (ref "D104") (pin "2") (pinfunction "2_2") (pintype "unspecified"))
      (node (ref "J101") (pin "6") (pinfunction "DP1_6") (pintype "unspecified"))
      (node (ref "J101") (pin "8") (pinfunction "DP2_8") (pintype "unspecified"))
      (node (ref "R111") (pin "1") (pinfunction "1_1") (pintype "input"))
    )
    (net (code "14") (name "ENC1_A") (class "Default")
      (node (ref "C203") (pin "2") (pinfunction "2_2") (pintype "input"))
      (node (ref "R205") (pin "1") (pinfunction "1_1") (pintype "input"))
      (node (ref "U101") (pin "18") (pinfunction "GPIO15_18") (pintype "bidirectional"))
    )
    (net (code "15") (name "ENC1_B") (class "Default")
      (node (ref "C205") (pin "2") (pinfunction "2_2") (pintype "input"))
      (node (ref "R207") (pin "1") (pinfunction "1_1") (pintype "input"))
      (node (ref "U101") (pin "27") (pinfunction "GPIO16_27") (pintype "bidirectional"))
    )
    (net (code "16") (name "ENC1_SW") (class "Default")
      (node (ref "D210") (pin "2") (pinfunction "2_2") (pintype "input"))
      (node (ref "ENC201") (pin "2") (pinfunction "2_2") (pintype "input"))
    )
    (net (code "17") (name "GND") (class "Default")
      (node (ref "C101") (pin "1") (pinfunction "1_1") (pintype "unspecified"))
      (node (ref "C102") (pin "1") (pinfunction "1_1") (pintype "unspecified"))
      (node (ref "C103") (pin "1") (pinfunction "1_1") (pintype "unspecified"))
      (node (ref "C104") (pin "1") (pinfunction "1_1") (pintype "unspecified"))
      (node (ref "C105") (pin "1") (pinfunction "1_1") (pintype "unspecified"))
      (node (ref "C106") (pin "1") (pinfunction "1_1") (pintype "unspecified"))
      (node (ref "C107") (pin "1") (pinfunction "1_1") (pintype "unspecified"))
      (node (ref "C108") (pin "1") (pinfunction "1_1") (pintype "unspecified"))
      (node (ref "C109") (pin "1") (pinfunction "1_1") (pintype "unspecified"))
      (node (ref "C110") (pin "1") (pinfunction "1_1") (pintype "unspecified"))
      (node (ref "C111") (pin "1") (pinfunction "1_1") (pintype "unspecified"))
      (node (ref "C112") (pin "1") (pinfunction "1_1") (pintype "unspecified"))
      (node (ref "C113") (pin "1") (pinfunction "1_1") (pintype "unspecified"))
      (node (ref "C114") (pin "1") (pinfunction "1_1") (pintype "unspecified"))
      (node (ref "C115") (pin "1") (pinfunction "1_1") (pintype "unspecified"))
      (node (ref "C116") (pin "1") (pinfunction "1_1") (pintype "unspecified"))
      (node (ref "C117") (pin "1") (pinfunction "1_1") (pintype "unspecified"))
      (node (ref "C118") (pin "1") (pinfunction "1_1") (pintype "unspecified"))
      (node (ref "C119") (pin "1") (pinfunction "1_1") (pintype "unspecified"))
      (node (ref "C120") (pin "1") (pinfunction "1_1") (pintype "unspecified"))
      (node (ref "C121") (pin "1") (pinfunction "1_1") (pintype "unspecified"))
      (node (ref "C123") (pin "2") (pinfunction "2_2") (pintype "unspecified"))
      (node (ref "C124") (pin "2") (pinfunction "2_2") (pintype "unspecified"))
      (node (ref "C125") (pin "1") (pinfunction "1_1") (pintype "unspecified"))
      (node (ref "C126") (pin "1") (pinfunction "1_1") (pintype "unspecified"))
      (node (ref "C127") (pin "1") (pinfunction "1_1") (pintype "unspecified"))
      (node (ref "C201") (pin "1") (pinfunction "1_1") (pintype "unspecified"))
      (node (ref "C203") (pin "1") (pinfunction "1_1") (pintype "input"))
      (node (ref "C205") (pin "1") (pinfunction "1_1") (pintype "input"))
      (node (ref "C210") (pin "1") (pinfunction "1_1") (pintype "unspecified"))
      (node (ref "C211") (pin "1") (pinfunction "1_1") (pintype "unspecified"))
      (node (ref "C212") (pin "1") (pinfunction "1_1") (pintype "unspecified"))
      (node (ref "C213") (pin "1") (pinfunction "1_1") (pintype "unspecified"))
      (node (ref "C214") (pin "1") (pinfunction "1_1") (pintype "unspecified"))
      (node (ref "C215") (pin "1") (pinfunction "1_1") (pintype "unspecified"))
      (node (ref "D101") (pin "2") (pinfunction "2_2") (pintype "unspecified"))
      (node (ref "D102") (pin "1") (pinfunction "1_1") (pintype "unspecified"))
      (node (ref "D103") (pin "1") (pinfunction "1_1") (pintype "unspecified"))
      (node (ref "D104") (pin "1") (pinfunction "1_1") (pintype "unspecified"))
      (node (ref "ENC201") (pin "3") (pinfunction "3_3") (pintype "input"))
      (node (ref "ENC201") (pin "4") (pinfunction "4_4") (pintype "input"))
      (node (ref "ENC201") (pin "C") (pinfunction "C_C") (pintype "input"))
      (node (ref "J101") (pin "1") (pinfunction "GND_1") (pintype "unspecified"))
      (node (ref "J101") (pin "12") (pinfunction "GND_12") (pintype "unspecified"))
      (node (ref "J101") (pin "13") (pinfunction "SHELL_13") (pintype "unspecified"))
      (node (ref "J101") (pin "14") (pinfunction "SHELL_14") (pintype "unspecified"))
      (node (ref "J102") (pin "2") (pinfunction "2_2") (pintype "input"))
      (node (ref "LED102") (pin "2") (pinfunction "K_2") (pintype "unspecified"))
      (node (ref "LED103") (pin "2") (pinfunction "-_2") (pintype "unspecified"))
      (node (ref "LED201") (pin "3") (pinfunction "GND_3") (pintype "unspecified"))
      (node (ref "LED202") (pin "3") (pinfunction "GND_3") (pintype "unspecified"))
      (node (ref "LED203") (pin "3") (pinfunction "GND_3") (pintype "unspecified"))
      (node (ref "LED204") (pin "3") (pinfunction "GND_3") (pintype "unspecified"))
      (node (ref "LED205") (pin "3") (pinfunction "GND_3") (pintype "unspecified"))
      (node (ref "LED206") (pin "3") (pinfunction "GND_3") (pintype "unspecified"))
      (node (ref "MH201") (pin "1") (pinfunction "1_1") (pintype "input"))
      (node (ref "MH202") (pin "1") (pinfunction "1_1") (pintype "input"))
      (node (ref "MH203") (pin "1") (pinfunction "1_1") (pintype "input"))
      (node (ref "MH204") (pin "1") (pinfunction "1_1") (pintype "input"))
      (node (ref "MH205") (pin "1") (pinfunction "1_1") (pintype "input"))
      (node (ref "MH206") (pin "1") (pinfunction "1_1") (pintype "input"))
      (node (ref "MH207") (pin "1") (pinfunction "1_1") (pintype "input"))
      (node (ref "MH208") (pin "1") (pinfunction "1_1") (pintype "input"))
      (node (ref "R113") (pin "2") (pinfunction "2_2") (pintype "input"))
      (node (ref "R116") (pin "1") (pinfunction "1_1") (pintype "input"))
      (node (ref "SW101") (pin "1") (pinfunction "A_1") (pintype "unspecified"))
      (node (ref "SW101") (pin "2") (pinfunction "B_2") (pintype "unspecified"))
      (node (ref "SW102") (pin "1") (pinfunction "A_1") (pintype "unspecified"))
      (node (ref "SW102") (pin "2") (pinfunction "B_2") (pintype "unspecified"))
      (node (ref "U101") (pin "19") (pinfunction "TESTEN_19") (pintype "unspecified"))
      (node (ref "U101") (pin "57") (pinfunction "GND_57") (pintype "bidirectional"))
      (node (ref "U102") (pin "2") (pinfunction "GND_2") (pintype "unspecified"))
      (node (ref "U102") (pin "4") (pinfunction "GND_4") (pintype "unspecified"))
      (node (ref "U103") (pin "4") (pinfunction "GND_4") (pintype "unspecified"))
      (node (ref "U104") (pin "3") (pinfunction "GND_3") (pintype "unspecified"))
      (node (ref "Y101") (pin "2") (pinfunction "GND_2") (pintype "input"))
      (node (ref "Y101") (pin "4") (pinfunction "GND_4") (pintype "input"))
    )
    (net (code "18") (name "LED0_BUF") (class "Default")
      (node (ref "R118") (pin "2") (pinfunction "2_2") (pintype "input"))
      (node (ref "U104") (pin "1") (pinfunction "NC_1") (pintype "unspecified"))
      (node (ref "U104") (pin "2") (pinfunction "A_2") (pintype "unspecified"))
    )
    (net (code "19") (name "LED0_DIN") (class "Default")
      (node (ref "LED201") (pin "4") (pinfunction "DIN_4") (pintype "unspecified"))
      (node (ref "U104") (pin "4") (pinfunction "Y_4") (pintype "unspecified"))
    )
    (net (code "20") (name "LED0_RES") (class "Default")
      (node (ref "R118") (pin "1") (pinfunction "1_1") (pintype "input"))
      (node (ref "U101") (pin "36") (pinfunction "GPIO24_36") (pintype "bidirectional"))
    )
    (net (code "21") (name "LED1_DIN") (class "Default")
      (node (ref "LED201") (pin "2") (pinfunction "DOUT_2") (pintype "unspecified"))
      (node (ref "LED202") (pin "4") (pinfunction "DIN_4") (pintype "unspecified"))
    )
    (net (code "22") (name "LED2_DIN") (class "Default")
      (node (ref "LED202") (pin "2") (pinfunction "DOUT_2") (pintype "unspecified"))
      (node (ref "LED203") (pin "4") (pinfunction "DIN_4") (pintype "unspecified"))
    )
    (net (code "23") (name "LED3_DIN") (class "Default")
      (node (ref "LED203") (pin "2") (pinfunction "DOUT_2") (pintype "unspecified"))
      (node (ref "LED204") (pin "4") (pinfunction "DIN_4") (pintype "unspecified"))
    )
    (net (code "24") (name "LED4_DIN") (class "Default")
      (node (ref "LED204") (pin "2") (pinfunction "DOUT_2") (pintype "unspecified"))
      (node (ref "LED205") (pin "4") (pinfunction "DIN_4") (pintype "unspecified"))
    )
    (net (code "25") (name "LED5_DIN") (class "Default")
      (node (ref "LED205") (pin "2") (pinfunction "DOUT_2") (pintype "unspecified"))
      (node (ref "LED206") (pin "4") (pinfunction "DIN_4") (pintype "unspecified"))
    )
    (net (code "26") (name "Net-(D201-Pad2)") (class "Default")
      (node (ref "D201") (pin "2") (pinfunction "2_2") (pintype "input"))
      (node (ref "J201") (pin "2") (pinfunction "2_2") (pintype "input"))
    )
    (net (code "27") (name "Net-(D202-Pad2)") (class "Default")
      (node (ref "D202") (pin "2") (pinfunction "2_2") (pintype "input"))
      (node (ref "J202") (pin "2") (pinfunction "2_2") (pintype "input"))
    )
    (net (code "28") (name "Net-(D203-Pad2)") (class "Default")
      (node (ref "D203") (pin "2") (pinfunction "2_2") (pintype "input"))
      (node (ref "J203") (pin "2") (pinfunction "2_2") (pintype "input"))
    )
    (net (code "29") (name "Net-(D204-Pad2)") (class "Default")
      (node (ref "D204") (pin "2") (pinfunction "2_2") (pintype "input"))
      (node (ref "J204") (pin "2") (pinfunction "2_2") (pintype "input"))
    )
    (net (code "30") (name "Net-(D205-Pad2)") (class "Default")
      (node (ref "D205") (pin "2") (pinfunction "2_2") (pintype "input"))
      (node (ref "J205") (pin "2") (pinfunction "2_2") (pintype "input"))
    )
    (net (code "31") (name "Net-(D206-Pad2)") (class "Default")
      (node (ref "D206") (pin "2") (pinfunction "2_2") (pintype "input"))
      (node (ref "J206") (pin "2") (pinfunction "2_2") (pintype "input"))
    )
    (net (code "32") (name "Net-(ENC201-PadA)") (class "Default")
      (node (ref "ENC201") (pin "A") (pinfunction "A_A") (pintype "input"))
      (node (ref "R201") (pin "1") (pinfunction "1_1") (pintype "input"))
      (node (ref "R205") (pin "2") (pinfunction "2_2") (pintype "input"))
    )
    (net (code "33") (name "Net-(ENC201-PadB)") (class "Default")
      (node (ref "ENC201") (pin "B") (pinfunction "B_B") (pintype "input"))
      (node (ref "R202") (pin "1") (pinfunction "1_1") (pintype "input"))
      (node (ref "R207") (pin "2") (pinfunction "2_2") (pintype "input"))
    )
    (net (code "34") (name "Net-(J101-CC1)") (class "Default")
      (node (ref "J101") (pin "4") (pinfunction "CC1_4") (pintype "unspecified"))
      (node (ref "R113") (pin "1") (pinfunction "1_1") (pintype "input"))
    )
    (net (code "35") (name "Net-(J101-CC2)") (class "Default")
      (node (ref "J101") (pin "10") (pinfunction "CC2_10") (pintype "unspecified"))
      (node (ref "R116") (pin "2") (pinfunction "2_2") (pintype "input"))
    )
    (net (code "36") (name "Net-(LED101---Pad2)") (class "Default")
      (node (ref "LED101") (pin "2") (pinfunction "-_2") (pintype "unspecified"))
      (node (ref "R103") (pin "1") (pinfunction "1_1") (pintype "input"))
    )
    (net (code "37") (name "Net-(LED101---Pad3)") (class "Default")
      (node (ref "LED101") (pin "3") (pinfunction "-_3") (pintype "unspecified"))
      (node (ref "R104") (pin "1") (pinfunction "1_1") (pintype "input"))
    )
    (net (code "38") (name "Net-(LED101---Pad4)") (class "Default")
      (node (ref "LED101") (pin "4") (pinfunction "-_4") (pintype "unspecified"))
      (node (ref "R105") (pin "1") (pinfunction "1_1") (pintype "input"))
    )
    (net (code "39") (name "Net-(LED102-A)") (class "Default")
      (node (ref "LED102") (pin "1") (pinfunction "A_1") (pintype "unspecified"))
      (node (ref "R101") (pin "1") (pinfunction "1_1") (pintype "input"))
    )
    (net (code "40") (name "Net-(LED103-+)") (class "Default")
      (node (ref "LED103") (pin "1") (pinfunction "+_1") (pintype "unspecified"))
      (node (ref "R102") (pin "1") (pinfunction "1_1") (pintype "input"))
    )
    (net (code "41") (name "Net-(SW101-C)") (class "Default")
      (node (ref "R122") (pin "1") (pinfunction "1_1") (pintype "input"))
      (node (ref "R124") (pin "1") (pinfunction "1_1") (pintype "input"))
      (node (ref "SW101") (pin "3") (pinfunction "C_3") (pintype "unspecified"))
      (node (ref "SW101") (pin "4") (pinfunction "D_4") (pintype "unspecified"))
    )
    (net (code "42") (name "Net-(SW102-C)") (class "Default")
      (node (ref "R123") (pin "1") (pinfunction "1_1") (pintype "input"))
      (node (ref "R125") (pin "1") (pinfunction "1_1") (pintype "input"))
      (node (ref "SW102") (pin "3") (pinfunction "C_3") (pintype "unspecified"))
      (node (ref "SW102") (pin "4") (pinfunction "D_4") (pintype "unspecified"))
    )
    (net (code "43") (name "QSPI_SCLK") (class "Default")
      (node (ref "U101") (pin "52") (pinfunction "QSPI_SCLK_52") (pintype "output"))
      (node (ref "U103") (pin "6") (pinfunction "CLK_6") (pintype "unspecified"))
    )
    (net (code "44") (name "QSPI_SD0") (class "Default")
      (node (ref "U101") (pin "53") (pinfunction "QSPI_SD0_53") (pintype "bidirectional"))
      (node (ref "U103") (pin "5") (pinfunction "DI_5") (pintype "unspecified"))
    )
    (net (code "45") (name "QSPI_SD1") (class "Default")
      (node (ref "U101") (pin "55") (pinfunction "QSPI_SD1_55") (pintype "bidirectional"))
      (node (ref "U103") (pin "2") (pinfunction "DO_2") (pintype "unspecified"))
    )
    (net (code "46") (name "QSPI_SD2") (class "Default")
      (node (ref "U101") (pin "54") (pinfunction "QSPI_SD2_54") (pintype "bidirectional"))
      (node (ref "U103") (pin "3") (pinfunction "IO2_3") (pintype "unspecified"))
    )
    (net (code "47") (name "QSPI_SD3") (class "Default")
      (node (ref "U101") (pin "51") (pinfunction "QSPI_SD3_51") (pintype "bidirectional"))
      (node (ref "U103") (pin "7") (pinfunction "IO3_7") (pintype "unspecified"))
    )
    (net (code "48") (name "QSPI_SS") (class "Default")
      (node (ref "R124") (pin "2") (pinfunction "2_2") (pintype "input"))
      (node (ref "U101") (pin "56") (pinfunction "QSPI_SS_56") (pintype "bidirectional"))
      (node (ref "U103") (pin "1") (pinfunction "CS#_1") (pintype "unspecified"))
    )
    (net (code "49") (name "RESET_N") (class "Default")
      (node (ref "C126") (pin "2") (pinfunction "2_2") (pintype "unspecified"))
      (node (ref "R125") (pin "2") (pinfunction "2_2") (pintype "input"))
      (node (ref "U101") (pin "26") (pinfunction "RUN_26") (pintype "input"))
    )
    (net (code "50") (name "ROW0") (class "Default")
      (node (ref "D201") (pin "1") (pinfunction "1_1") (pintype "input"))
      (node (ref "D202") (pin "1") (pinfunction "1_1") (pintype "input"))
      (node (ref "D210") (pin "1") (pinfunction "1_1") (pintype "input"))
      (node (ref "R114") (pin "2") (pinfunction "2_2") (pintype "input"))
    )
    (net (code "51") (name "ROW0_R") (class "Default")
      (node (ref "C117") (pin "2") (pinfunction "2_2") (pintype "unspecified"))
      (node (ref "R114") (pin "1") (pinfunction "1_1") (pintype "input"))
      (node (ref "U101") (pin "11") (pinfunction "GPIO8_11") (pintype "bidirectional"))
    )
    (net (code "52") (name "ROW1") (class "Default")
      (node (ref "D203") (pin "1") (pinfunction "1_1") (pintype "input"))
      (node (ref "D204") (pin "1") (pinfunction "1_1") (pintype "input"))
      (node (ref "R115") (pin "2") (pinfunction "2_2") (pintype "input"))
    )
    (net (code "53") (name "ROW1_R") (class "Default")
      (node (ref "C118") (pin "2") (pinfunction "2_2") (pintype "unspecified"))
      (node (ref "R115") (pin "1") (pinfunction "1_1") (pintype "input"))
      (node (ref "U101") (pin "12") (pinfunction "GPIO9_12") (pintype "bidirectional"))
    )
    (net (code "54") (name "ROW2") (class "Default")
      (node (ref "D205") (pin "1") (pinfunction "1_1") (pintype "input"))
      (node (ref "D206") (pin "1") (pinfunction "1_1") (pintype "input"))
      (node (ref "R117") (pin "2") (pinfunction "2_2") (pintype "input"))
    )
    (net (code "55") (name "ROW2_R") (class "Default")
      (node (ref "C121") (pin "2") (pinfunction "2_2") (pintype "unspecified"))
      (node (ref "R117") (pin "1") (pinfunction "1_1") (pintype "input"))
      (node (ref "U101") (pin "13") (pinfunction "GPIO10_13") (pintype "bidirectional"))
    )
    (net (code "56") (name "SWCLK") (class "Default")
      (node (ref "J102") (pin "1") (pinfunction "1_1") (pintype "input"))
      (node (ref "U101") (pin "24") (pinfunction "SWCLK_24") (pintype "output"))
    )
    (net (code "57") (name "SWDIO") (class "Default")
      (node (ref "J102") (pin "3") (pinfunction "3_3") (pintype "input"))
      (node (ref "U101") (pin "25") (pinfunction "SWD_25") (pintype "bidirectional"))
    )
    (net (code "58") (name "USB_N") (class "Default")
      (node (ref "R109") (pin "2") (pinfunction "2_2") (pintype "input"))
      (node (ref "U101") (pin "46") (pinfunction "USB_DM_46") (pintype "bidirectional"))
    )
    (net (code "59") (name "USB_P") (class "Default")
      (node (ref "R111") (pin "2") (pinfunction "2_2") (pintype "input"))
      (node (ref "U101") (pin "47") (pinfunction "USB_DP_47") (pintype "bidirectional"))
    )
    (net (code "60") (name "USER_LED1") (class "Default")
      (node (ref "R102") (pin "2") (pinfunction "2_2") (pintype "input"))
      (node (ref "U101") (pin "37") (pinfunction "GPIO25_37") (pintype "bidirectional"))
    )
    (net (code "61") (name "USER_LED2_B") (class "Default")
      (node (ref "R105") (pin "2") (pinfunction "2_2") (pintype "input"))
      (node (ref "U101") (pin "40") (pinfunction "GPIO28_ADC2_40") (pintype "bidirectional"))
    )
    (net (code "62") (name "USER_LED2_G") (class "Default")
      (node (ref "R104") (pin "2") (pinfunction "2_2") (pintype "input"))
      (node (ref "U101") (pin "39") (pinfunction "GPIO27_ADC1_39") (pintype "bidirectional"))
    )
    (net (code "63") (name "USER_LED2_R") (class "Default")
      (node (ref "R103") (pin "2") (pinfunction "2_2") (pintype "input"))
      (node (ref "U101") (pin "38") (pinfunction "GPIO26_ADC0_38") (pintype "bidirectional"))
    )
    (net (code "64") (name "XIN") (class "Default")
      (node (ref "C123") (pin "1") (pinfunction "1_1") (pintype "unspecified"))
      (node (ref "R120") (pin "2") (pinfunction "2_2") (pintype "input"))
      (node (ref "U101") (pin "20") (pinfunction "XIN_20") (pintype "input"))
      (node (ref "Y101") (pin "1") (pinfunction "1_1") (pintype "input"))
    )
    (net (code "65") (name "XOUT") (class "Default")
      (node (ref "R120") (pin "1") (pinfunction "1_1") (pintype "input"))
      (node (ref "R121") (pin "2") (pinfunction "2_2") (pintype "input"))
      (node (ref "U101") (pin "21") (pinfunction "XOUT_21") (pintype "unspecified"))
    )
    (net (code "66") (name "X_R") (class "Default")
      (node (ref "C124") (pin "1") (pinfunction "1_1") (pintype "unspecified"))
      (node (ref "R121") (pin "1") (pinfunction "1_1") (pintype "input"))
      (node (ref "Y101") (pin "3") (pinfunction "3_3") (pintype "input"))
    )
    (net (code "67") (name "unconnected-(J101-SBU1-Pad9)") (class "Default")
      (node (ref "J101") (pin "9") (pinfunction "SBU1_9") (pintype "unspecified+no_connect"))
    )
    (net (code "68") (name "unconnected-(J101-SBU2-Pad3)") (class "Default")
      (node (ref "J101") (pin "3") (pinfunction "SBU2_3") (pintype "unspecified+no_connect"))
    )
    (net (code "69") (name "unconnected-(LED206-DOUT-Pad2)") (class "Default")
      (node (ref "LED206") (pin "2") (pinfunction "DOUT_2") (pintype "unspecified+no_connect"))
    )
    (net (code "70") (name "unconnected-(U101-GPIO3-Pad5)") (class "Default")
      (node (ref "U101") (pin "5") (pinfunction "GPIO3_5") (pintype "bidirectional+no_connect"))
    )
    (net (code "71") (name "unconnected-(U101-GPIO4-Pad6)") (class "Default")
      (node (ref "U101") (pin "6") (pinfunction "GPIO4_6") (pintype "bidirectional+no_connect"))
    )
    (net (code "72") (name "unconnected-(U101-GPIO5-Pad7)") (class "Default")
      (node (ref "U101") (pin "7") (pinfunction "GPIO5_7") (pintype "bidirectional+no_connect"))
    )
    (net (code "73") (name "unconnected-(U101-GPIO6-Pad8)") (class "Default")
      (node (ref "U101") (pin "8") (pinfunction "GPIO6_8") (pintype "bidirectional+no_connect"))
    )
    (net (code "74") (name "unconnected-(U101-GPIO7-Pad9)") (class "Default")
      (node (ref "U101") (pin "9") (pinfunction "GPIO7_9") (pintype "bidirectional+no_connect"))
    )
    (net (code "75") (name "unconnected-(U101-GPIO11-Pad14)") (class "Default")
      (node (ref "U101") (pin "14") (pinfunction "GPIO11_14") (pintype "bidirectional+no_connect"))
    )
    (net (code "76") (name "unconnected-(U101-GPIO12-Pad15)") (class "Default")
      (node (ref "U101") (pin "15") (pinfunction "GPIO12_15") (pintype "bidirectional+no_connect"))
    )
    (net (code "77") (name "unconnected-(U101-GPIO13-Pad16)") (class "Default")
      (node (ref "U101") (pin "16") (pinfunction "GPIO13_16") (pintype "bidirectional+no_connect"))
    )
    (net (code "78") (name "unconnected-(U101-GPIO14-Pad17)") (class "Default")
      (node (ref "U101") (pin "17") (pinfunction "GPIO14_17") (pintype "bidirectional+no_connect"))
    )
    (net (code "79") (name "unconnected-(U101-GPIO17-Pad28)") (class "Default")
      (node (ref "U101") (pin "28") (pinfunction "GPIO17_28") (pintype "bidirectional+no_connect"))
    )
    (net (code "80") (name "unconnected-(U101-GPIO18-Pad29)") (class "Default")
      (node (ref "U101") (pin "29") (pinfunction "GPIO18_29") (pintype "bidirectional+no_connect"))
    )
    (net (code "81") (name "unconnected-(U101-GPIO19-Pad30)") (class "Default")
      (node (ref "U101") (pin "30") (pinfunction "GPIO19_30") (pintype "bidirectional+no_connect"))
    )
    (net (code "82") (name "unconnected-(U101-GPIO20-Pad31)") (class "Default")
      (node (ref "U101") (pin "31") (pinfunction "GPIO20_31") (pintype "bidirectional+no_connect"))
    )
    (net (code "83") (name "unconnected-(U101-GPIO21-Pad32)") (class "Default")
      (node (ref "U101") (pin "32") (pinfunction "GPIO21_32") (pintype "bidirectional+no_connect"))
    )
    (net (code "84") (name "unconnected-(U101-GPIO22-Pad34)") (class "Default")
      (node (ref "U101") (pin "34") (pinfunction "GPIO22_34") (pintype "bidirectional+no_connect"))
    )
    (net (code "85") (name "unconnected-(U101-GPIO23-Pad35)") (class "Default")
      (node (ref "U101") (pin "35") (pinfunction "GPIO23_35") (pintype "bidirectional+no_connect"))
    )
    (net (code "86") (name "unconnected-(U101-GPIO29_ADC3-Pad41)") (class "Default")
      (node (ref "U101") (pin "41") (pinfunction "GPIO29_ADC3_41") (pintype "bidirectional+no_connect"))
    )
  )
)
